# 19_CAN.net
KiCad netlist of a schematic drawn in Altium Designer
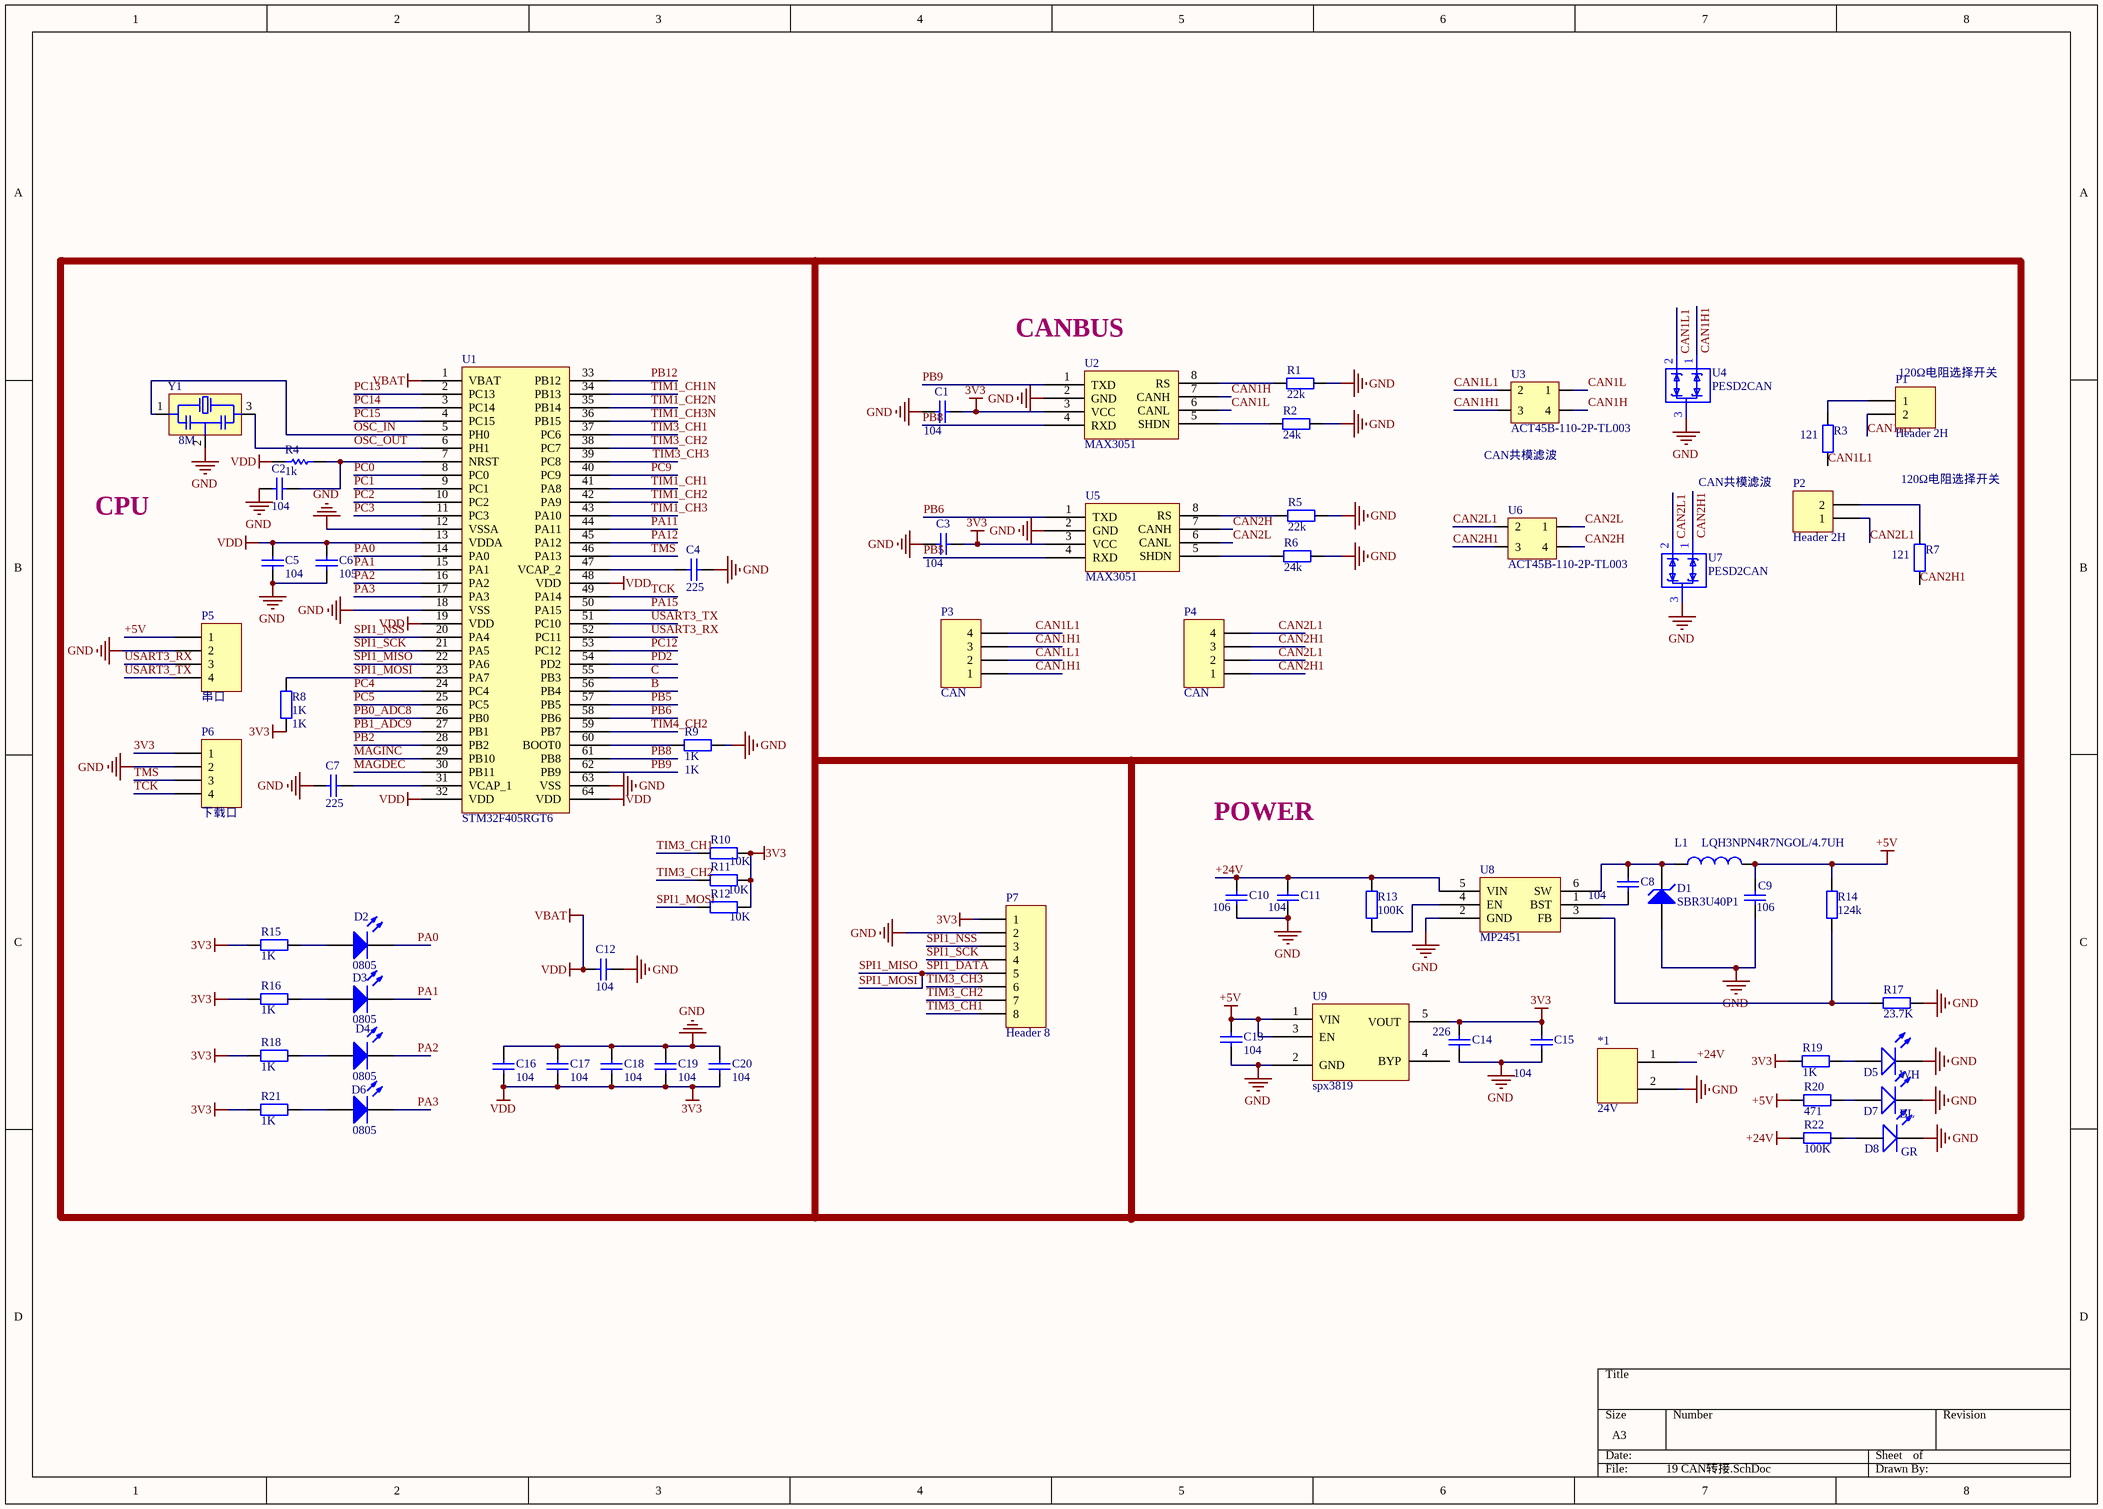
[diagram p0: 19 CAN转接.SchDoc]

(export (version "E")
  (design (tool "Eeschema 10.0.6"))
  (components
    (comp (ref "*1") (value "24V") (footprint "J-XH-2A") (libsource (lib "ACTION原理图库") (part "插件")))
    (comp (ref "C1")
      (value "104")
      (footprint "0402_C")
      (description "贴片电容")
      (libsource (lib "Cap0603") (part "0603 100nF (104) 10% 50V"))
    )
    (comp (ref "C2")
      (value "104")
      (footprint "0603_C")
      (description "Capacitor")
      (libsource (lib "Miscellaneous Devices") (part "Cap"))
    )
    (comp (ref "C3")
      (value "104")
      (footprint "0402_C")
      (description "贴片电容")
      (libsource (lib "Cap0603") (part "0603 100nF (104) 10% 50V"))
    )
    (comp (ref "C4")
      (value "225")
      (footprint "0603_C")
      (description "Capacitor")
      (libsource (lib "Miscellaneous Devices") (part "Cap"))
    )
    (comp (ref "C5")
      (value "104")
      (footprint "0603_C")
      (description "Capacitor")
      (libsource (lib "Miscellaneous Devices") (part "Cap"))
    )
    (comp (ref "C6")
      (value "105")
      (footprint "0603_C")
      (description "Capacitor")
      (libsource (lib "Miscellaneous Devices") (part "Cap"))
    )
    (comp (ref "C7")
      (value "225")
      (footprint "0603_C")
      (description "Capacitor")
      (libsource (lib "Miscellaneous Devices") (part "Cap"))
    )
    (comp (ref "C8")
      (value "104")
      (footprint "0603_C")
      (description "贴片电容")
      (libsource (lib "Cap0603") (part "0603 100nF (104) 10% 50V"))
    )
    (comp (ref "C9")
      (value "106")
      (footprint "0805_C")
      (description "贴片电容")
      (libsource (lib "Cap0805") (part "0805 10uF (106) 10% 25V"))
    )
    (comp (ref "C10")
      (value "106")
      (footprint "0805_C")
      (description "贴片电容")
      (libsource (lib "Cap0805") (part "0805 10uF (106) 10% 25V"))
    )
    (comp (ref "C11")
      (value "104")
      (footprint "0805_C")
      (description "贴片电容")
      (libsource (lib "Cap0805") (part "0805 100nF(104) 10% 50V"))
    )
    (comp (ref "C12")
      (value "104")
      (footprint "0603_C")
      (description "Capacitor")
      (libsource (lib "Miscellaneous Devices") (part "Cap"))
    )
    (comp (ref "C13")
      (value "104")
      (footprint "0603_C")
      (description "贴片电容")
      (libsource (lib "Cap0603") (part "0603 100nF (104) 10% 50V"))
    )
    (comp (ref "C14")
      (value "226")
      (footprint "0603_C")
      (description "贴片电容")
      (libsource (lib "Cap0603") (part "0603 22uF (226) 20% 6.3V"))
    )
    (comp (ref "C15")
      (value "104")
      (footprint "0603_C")
      (description "贴片电容")
      (libsource (lib "Cap0603") (part "0603 100nF (104) 10% 50V"))
    )
    (comp (ref "C16")
      (value "104")
      (footprint "0603_C")
      (description "Capacitor")
      (libsource (lib "Miscellaneous Devices") (part "Cap"))
    )
    (comp (ref "C17")
      (value "104")
      (footprint "0603_C")
      (description "Capacitor")
      (libsource (lib "Miscellaneous Devices") (part "Cap"))
    )
    (comp (ref "C18")
      (value "104")
      (footprint "0603_C")
      (description "Capacitor")
      (libsource (lib "Miscellaneous Devices") (part "Cap"))
    )
    (comp (ref "C19")
      (value "104")
      (footprint "0603_C")
      (description "Capacitor")
      (libsource (lib "Miscellaneous Devices") (part "Cap"))
    )
    (comp (ref "C20")
      (value "104")
      (footprint "0603_C")
      (description "Capacitor")
      (libsource (lib "Miscellaneous Devices") (part "Cap"))
    )
    (comp (ref "D1")
      (value "SBR3U40P1")
      (footprint "D-POWERDI123")
      (description "Zener Diode")
      (libsource (lib "Miscellaneous Devices") (part "D Zener"))
    )
    (comp (ref "D2")
      (value "0805")
      (footprint "0603_LED_S1")
      (description "发光二极管")
      (libsource (lib "LED") (part "0805 蓝灯"))
    )
    (comp (ref "D3")
      (value "0805")
      (footprint "0603_LED_S1")
      (description "发光二极管")
      (libsource (lib "LED") (part "0805 蓝灯"))
    )
    (comp (ref "D4")
      (value "0805")
      (footprint "0603_LED_S1")
      (description "发光二极管")
      (libsource (lib "LED") (part "0805 蓝灯"))
    )
    (comp (ref "D5")
      (value "WH")
      (footprint "0603_LED_S1")
      (description "发光二极管")
      (libsource (lib "LED") (part "0805 白灯"))
    )
    (comp (ref "D6")
      (value "0805")
      (footprint "0603_LED_S1")
      (description "发光二极管")
      (libsource (lib "LED") (part "0805 蓝灯"))
    )
    (comp (ref "D7")
      (value "BL")
      (footprint "0603_LED_S1")
      (description "发光二极管")
      (libsource (lib "LED") (part "0805 白灯"))
    )
    (comp (ref "D8")
      (value "GR")
      (footprint "0603_LED_S1")
      (description "发光二极管")
      (libsource (lib "LED") (part "0805 白灯"))
    )
    (comp (ref "L1")
      (value "LQH3NPN4R7NGOL/4.7UH")
      (footprint "1206_L")
      (description "4.7uh")
      (libsource (lib "Miscellaneous Devices") (part "Inductor"))
    )
    (comp (ref "P1")
      (value "Header 2H")
      (footprint "拨码开关贴片1位 小")
      (description "Header, 2-Pin, Right Angle")
      (fields (field (name "PUBLISHER") "Altium Limited"))
      (libsource (lib "Miscellaneous Connectors") (part "Header 2H"))
    )
    (comp (ref "P2")
      (value "Header 2H")
      (footprint "拨码开关贴片1位 小")
      (description "Header, 2-Pin, Right Angle")
      (fields (field (name "PUBLISHER") "Altium Limited"))
      (libsource (lib "") (part "Header 2H_1"))
    )
    (comp (ref "P3")
      (value "CAN")
      (footprint "J-GH-4P")
      (description "Header, 4-Pin")
      (libsource (lib "ACTION原理图库") (part "J-4PIN"))
    )
    (comp (ref "P4")
      (value "CAN")
      (footprint "J-GH-4P")
      (description "Header, 4-Pin")
      (libsource (lib "ACTION原理图库") (part "J-4PIN"))
    )
    (comp (ref "P5")
      (value "串口")
      (footprint "J-1.27-4P")
      (description "Header, 4-Pin")
      (libsource (lib "Miscellaneous Connectors") (part "Header 4"))
    )
    (comp (ref "P6")
      (value "下载口")
      (footprint "J-1.27-4P")
      (description "Header, 4-Pin")
      (libsource (lib "Miscellaneous Connectors") (part "Header 4"))
    )
    (comp (ref "P7")
      (value "Header 8")
      (footprint "J-GH-8P")
      (description "Header, 8-Pin")
      (fields (field (name "PUBLISHER") "Altium Limited"))
      (libsource (lib "Miscellaneous Connectors") (part "Header 8"))
    )
    (comp (ref "R1")
      (value "22k")
      (footprint "0603_R")
      (description "贴片电阻")
      (libsource (lib "") (part "0603 120Ω (1200) 1%_1"))
    )
    (comp (ref "R2")
      (value "24k")
      (footprint "0603_R")
      (description "贴片电阻")
      (libsource (lib "") (part "0603 120Ω (1200) 1%_2"))
    )
    (comp (ref "R3")
      (value "121")
      (footprint "0603_R")
      (description "贴片电阻")
      (libsource (lib "RES0603") (part "0603 120Ω (1200) 1%"))
    )
    (comp (ref "R4")
      (value "1k")
      (footprint "0603_R")
      (description "Semiconductor Resistor")
      (libsource (lib "大赛无线手柄") (part "Res Semi"))
    )
    (comp (ref "R5")
      (value "22k")
      (footprint "0603_R")
      (description "贴片电阻")
      (libsource (lib "") (part "0603 120Ω (1200) 1%_1"))
    )
    (comp (ref "R6")
      (value "24k")
      (footprint "0603_R")
      (description "贴片电阻")
      (libsource (lib "") (part "0603 120Ω (1200) 1%_2"))
    )
    (comp (ref "R7")
      (value "121")
      (footprint "0603_R")
      (description "贴片电阻")
      (libsource (lib "RES0603") (part "0603 120Ω (1200) 1%"))
    )
    (comp (ref "R8")
      (value "1K")
      (footprint "0603_R")
      (description "Resistor")
      (fields (field (name "ALTIUM_VALUE") "1K"))
      (libsource (lib "Miscellaneous Devices") (part "Res2"))
    )
    (comp (ref "R9")
      (value "1K")
      (footprint "0603_R")
      (description "Resistor")
      (fields (field (name "ALTIUM_VALUE") "1K"))
      (libsource (lib "") (part "Res2_2"))
    )
    (comp (ref "R10")
      (value "10K")
      (footprint "0603_R")
      (description "贴片电阻")
      (libsource (lib "RES0603") (part "0603 1KΩ (1001) 1%"))
    )
    (comp (ref "R11")
      (value "10K")
      (footprint "0603_R")
      (description "贴片电阻")
      (libsource (lib "RES0603") (part "0603 1KΩ (1001) 1%"))
    )
    (comp (ref "R12")
      (value "10K")
      (footprint "0603_R")
      (description "贴片电阻")
      (libsource (lib "RES0603") (part "0603 1KΩ (1001) 1%"))
    )
    (comp (ref "R13")
      (value "100K")
      (footprint "0603_R")
      (description "贴片电阻")
      (libsource (lib "RES0603") (part "0603 100KΩ (1003) 1%"))
    )
    (comp (ref "R14") (value "124k") (footprint "0603_R") (libsource (lib "") (part "Res2_3")))
    (comp (ref "R15")
      (value "1K")
      (footprint "0603_R")
      (description "Resistor")
      (libsource (lib "Free Documents") (part "Res2"))
    )
    (comp (ref "R16")
      (value "1K")
      (footprint "0603_R")
      (description "Resistor")
      (libsource (lib "Free Documents") (part "Res2"))
    )
    (comp (ref "R17")
      (value "23.7K")
      (footprint "0603_R")
      (description "Resistor")
      (libsource (lib "") (part "Res2_1"))
    )
    (comp (ref "R18")
      (value "1K")
      (footprint "0603_R")
      (description "Resistor")
      (libsource (lib "Free Documents") (part "Res2"))
    )
    (comp (ref "R19")
      (value "1K")
      (footprint "0603_R")
      (description "贴片电阻")
      (libsource (lib "RES0603") (part "0603 1KΩ (1001) 1%"))
    )
    (comp (ref "R20")
      (value "471")
      (footprint "0603_R")
      (description "贴片电阻")
      (libsource (lib "RES0603") (part "0603 2KΩ (2001) 1%"))
    )
    (comp (ref "R21")
      (value "1K")
      (footprint "0603_R")
      (description "Resistor")
      (libsource (lib "Free Documents") (part "Res2"))
    )
    (comp (ref "R22")
      (value "100K")
      (footprint "0603_R")
      (description "贴片电阻")
      (libsource (lib "RES0603") (part "0603 10KΩ (1002) 1%"))
    )
    (comp (ref "U1")
      (value "STM32F405RGT6")
      (footprint "LQFP-64")
      (libsource (lib "陀螺仪 元件") (part "STM32F405RGT7"))
    )
    (comp (ref "U2")
      (value "MAX3051")
      (footprint "SOT-23-8")
      (libsource (lib "ACTION原理图库17.7.20修改版") (part "MAX3051EKA"))
    )
    (comp (ref "U3")
      (value "ACT45B-110-2P-TL003")
      (footprint "ACT45B")
      (description "B82793C0/S0")
      (libsource (lib "ACTION原理图库") (part "扼流线圈"))
    )
    (comp (ref "U4") (value "PESD2CAN") (footprint "SOT-233") (libsource (lib "英飞凌电流检测") (part "PESD2CAN")))
    (comp (ref "U5")
      (value "MAX3051")
      (footprint "SOT-23-8")
      (libsource (lib "ACTION原理图库17.7.20修改版") (part "MAX3051EKA"))
    )
    (comp (ref "U6")
      (value "ACT45B-110-2P-TL003")
      (footprint "ACT45B")
      (description "B82793C0/S0")
      (libsource (lib "ACTION原理图库") (part "扼流线圈"))
    )
    (comp (ref "U7") (value "PESD2CAN") (footprint "SOT-233") (libsource (lib "英飞凌电流检测") (part "PESD2CAN")))
    (comp (ref "U8") (value "MP2451") (footprint "SOT-236") (libsource (lib "stm32f103vet6") (part "MP2451")))
    (comp (ref "U9")
      (value "spx3819")
      (footprint "SOT-235")
      (description "spx5205")
      (libsource (lib "无刷01") (part "spx5205"))
    )
    (comp (ref "Y1") (value "8M") (footprint "X-CSTCE8M") (libsource (lib "LPC11Cxx") (part "TXAL-3")))
  )
  (nets
    (net (code "1") (name "+5V") (class "Default")
      (node (ref "C13") (pin "2") (pinfunction "2_2") (pintype "passive"))
      (node (ref "C9") (pin "2") (pinfunction "2_2") (pintype "passive"))
      (node (ref "L1") (pin "2") (pinfunction "2_2") (pintype "passive"))
      (node (ref "P5") (pin "1") (pinfunction "1_1") (pintype "passive"))
      (node (ref "R14") (pin "1") (pinfunction "1_1") (pintype "passive"))
      (node (ref "R20") (pin "1") (pinfunction "1_1") (pintype "passive"))
      (node (ref "U9") (pin "1") (pinfunction "VIN_1") (pintype "passive"))
      (node (ref "U9") (pin "3") (pinfunction "EN_3") (pintype "passive"))
    )
    (net (code "2") (name "+24V") (class "Default")
      (node (ref "*1") (pin "1") (pintype "passive"))
      (node (ref "C10") (pin "2") (pinfunction "2_2") (pintype "passive"))
      (node (ref "C11") (pin "2") (pinfunction "2_2") (pintype "passive"))
      (node (ref "R13") (pin "2") (pinfunction "2_2") (pintype "passive"))
      (node (ref "R22") (pin "1") (pinfunction "1_1") (pintype "passive"))
      (node (ref "U8") (pin "5") (pinfunction "VIN_5") (pintype "passive"))
    )
    (net (code "3") (name "/B") (class "Default")
      (node (ref "U1") (pin "56") (pinfunction "PB4_56") (pintype "passive"))
    )
    (net (code "4") (name "/C") (class "Default")
      (node (ref "U1") (pin "55") (pinfunction "PB3_55") (pintype "passive"))
    )
    (net (code "5") (name "/CAN1H") (class "Default")
      (node (ref "U2") (pin "7") (pinfunction "CANH_7") (pintype "passive"))
      (node (ref "U3") (pin "4") (pinfunction "4_4") (pintype "passive"))
    )
    (net (code "6") (name "/CAN1H1") (class "Default")
      (node (ref "P1") (pin "2") (pinfunction "2_2") (pintype "passive"))
      (node (ref "P3") (pin "1") (pinfunction "1_1") (pintype "passive"))
      (node (ref "P3") (pin "3") (pinfunction "3_3") (pintype "passive"))
      (node (ref "U3") (pin "3") (pinfunction "3_3") (pintype "passive"))
      (node (ref "U4") (pin "1") (pinfunction "1_1") (pintype "passive"))
    )
    (net (code "7") (name "/CAN1L") (class "Default")
      (node (ref "U2") (pin "6") (pinfunction "CANL_6") (pintype "passive"))
      (node (ref "U3") (pin "1") (pinfunction "1_1") (pintype "passive"))
    )
    (net (code "8") (name "/CAN1L1") (class "Default")
      (node (ref "P3") (pin "2") (pinfunction "2_2") (pintype "passive"))
      (node (ref "P3") (pin "4") (pinfunction "4_4") (pintype "passive"))
      (node (ref "R3") (pin "1") (pinfunction "1_1") (pintype "passive"))
      (node (ref "U3") (pin "2") (pinfunction "2_2") (pintype "passive"))
      (node (ref "U4") (pin "2") (pinfunction "2_2") (pintype "passive"))
    )
    (net (code "9") (name "/CAN2H") (class "Default")
      (node (ref "U5") (pin "7") (pinfunction "CANH_7") (pintype "passive"))
      (node (ref "U6") (pin "4") (pinfunction "4_4") (pintype "passive"))
    )
    (net (code "10") (name "/CAN2H1") (class "Default")
      (node (ref "P4") (pin "1") (pinfunction "1_1") (pintype "passive"))
      (node (ref "P4") (pin "3") (pinfunction "3_3") (pintype "passive"))
      (node (ref "R7") (pin "1") (pinfunction "1_1") (pintype "passive"))
      (node (ref "U6") (pin "3") (pinfunction "3_3") (pintype "passive"))
      (node (ref "U7") (pin "1") (pinfunction "1_1") (pintype "passive"))
    )
    (net (code "11") (name "/CAN2L") (class "Default")
      (node (ref "U5") (pin "6") (pinfunction "CANL_6") (pintype "passive"))
      (node (ref "U6") (pin "1") (pinfunction "1_1") (pintype "passive"))
    )
    (net (code "12") (name "/CAN2L1") (class "Default")
      (node (ref "P2") (pin "1") (pinfunction "1_1") (pintype "passive"))
      (node (ref "P4") (pin "2") (pinfunction "2_2") (pintype "passive"))
      (node (ref "P4") (pin "4") (pinfunction "4_4") (pintype "passive"))
      (node (ref "U6") (pin "2") (pinfunction "2_2") (pintype "passive"))
      (node (ref "U7") (pin "2") (pinfunction "2_2") (pintype "passive"))
    )
    (net (code "13") (name "/MAGDEC") (class "Default")
      (node (ref "U1") (pin "30") (pinfunction "PB11_30") (pintype "passive"))
    )
    (net (code "14") (name "/MAGINC") (class "Default")
      (node (ref "U1") (pin "29") (pinfunction "PB10_29") (pintype "passive"))
    )
    (net (code "15") (name "/OSC_IN") (class "Default")
      (node (ref "U1") (pin "5") (pinfunction "PH0_5") (pintype "passive"))
      (node (ref "Y1") (pin "1") (pinfunction "OSCIN_1") (pintype "passive"))
    )
    (net (code "16") (name "/OSC_OUT") (class "Default")
      (node (ref "U1") (pin "6") (pinfunction "PH1_6") (pintype "passive"))
      (node (ref "Y1") (pin "3") (pinfunction "OSCOUT_3") (pintype "passive"))
    )
    (net (code "17") (name "/PA0") (class "Default")
      (node (ref "D2") (pin "K") (pinfunction "K_K") (pintype "passive"))
      (node (ref "U1") (pin "14") (pinfunction "PA0_14") (pintype "passive"))
    )
    (net (code "18") (name "/PA1") (class "Default")
      (node (ref "D3") (pin "K") (pinfunction "K_K") (pintype "passive"))
      (node (ref "U1") (pin "15") (pinfunction "PA1_15") (pintype "passive"))
    )
    (net (code "19") (name "/PA2") (class "Default")
      (node (ref "D4") (pin "K") (pinfunction "K_K") (pintype "passive"))
      (node (ref "U1") (pin "16") (pinfunction "PA2_16") (pintype "passive"))
    )
    (net (code "20") (name "/PA3") (class "Default")
      (node (ref "D6") (pin "K") (pinfunction "K_K") (pintype "passive"))
      (node (ref "U1") (pin "17") (pinfunction "PA3_17") (pintype "passive"))
    )
    (net (code "21") (name "/PA11") (class "Default")
      (node (ref "U1") (pin "44") (pinfunction "PA11_44") (pintype "passive"))
    )
    (net (code "22") (name "/PA12") (class "Default")
      (node (ref "U1") (pin "45") (pinfunction "PA12_45") (pintype "passive"))
    )
    (net (code "23") (name "/PA15") (class "Default")
      (node (ref "U1") (pin "50") (pinfunction "PA15_50") (pintype "passive"))
    )
    (net (code "24") (name "/PB0_ADC8") (class "Default")
      (node (ref "U1") (pin "26") (pinfunction "PB0_26") (pintype "passive"))
    )
    (net (code "25") (name "/PB1_ADC9") (class "Default")
      (node (ref "U1") (pin "27") (pinfunction "PB1_27") (pintype "passive"))
    )
    (net (code "26") (name "/PB2") (class "Default")
      (node (ref "U1") (pin "28") (pinfunction "PB2_28") (pintype "passive"))
    )
    (net (code "27") (name "/PB5") (class "Default")
      (node (ref "U1") (pin "57") (pinfunction "PB5_57") (pintype "passive"))
      (node (ref "U5") (pin "4") (pinfunction "RXD_4") (pintype "passive"))
    )
    (net (code "28") (name "/PB6") (class "Default")
      (node (ref "U1") (pin "58") (pinfunction "PB6_58") (pintype "passive"))
      (node (ref "U5") (pin "1") (pinfunction "TXD_1") (pintype "passive"))
    )
    (net (code "29") (name "/PB8") (class "Default")
      (node (ref "U1") (pin "61") (pinfunction "PB8_61") (pintype "passive"))
      (node (ref "U2") (pin "4") (pinfunction "RXD_4") (pintype "passive"))
    )
    (net (code "30") (name "/PB9") (class "Default")
      (node (ref "U1") (pin "62") (pinfunction "PB9_62") (pintype "passive"))
      (node (ref "U2") (pin "1") (pinfunction "TXD_1") (pintype "passive"))
    )
    (net (code "31") (name "/PB12") (class "Default")
      (node (ref "U1") (pin "33") (pinfunction "PB12_33") (pintype "passive"))
    )
    (net (code "32") (name "/PC0") (class "Default")
      (node (ref "U1") (pin "8") (pinfunction "PC0_8") (pintype "passive"))
    )
    (net (code "33") (name "/PC1") (class "Default")
      (node (ref "U1") (pin "9") (pinfunction "PC1_9") (pintype "passive"))
    )
    (net (code "34") (name "/PC2") (class "Default")
      (node (ref "U1") (pin "10") (pinfunction "PC2_10") (pintype "passive"))
    )
    (net (code "35") (name "/PC3") (class "Default")
      (node (ref "U1") (pin "11") (pinfunction "PC3_11") (pintype "passive"))
    )
    (net (code "36") (name "/PC4") (class "Default")
      (node (ref "U1") (pin "24") (pinfunction "PC4_24") (pintype "passive"))
    )
    (net (code "37") (name "/PC5") (class "Default")
      (node (ref "U1") (pin "25") (pinfunction "PC5_25") (pintype "passive"))
    )
    (net (code "38") (name "/PC9") (class "Default")
      (node (ref "U1") (pin "40") (pinfunction "PC9_40") (pintype "passive"))
    )
    (net (code "39") (name "/PC12") (class "Default")
      (node (ref "U1") (pin "53") (pinfunction "PC12_53") (pintype "passive"))
    )
    (net (code "40") (name "/PC13") (class "Default")
      (node (ref "U1") (pin "2") (pinfunction "PC13_2") (pintype "passive"))
    )
    (net (code "41") (name "/PC14") (class "Default")
      (node (ref "U1") (pin "3") (pinfunction "PC14_3") (pintype "passive"))
    )
    (net (code "42") (name "/PC15") (class "Default")
      (node (ref "U1") (pin "4") (pinfunction "PC15_4") (pintype "passive"))
    )
    (net (code "43") (name "/PD2") (class "Default")
      (node (ref "U1") (pin "54") (pinfunction "PD2_54") (pintype "passive"))
    )
    (net (code "44") (name "/SPI1_DATA") (class "Default")
      (node (ref "P7") (pin "5") (pinfunction "5_5") (pintype "passive"))
      (node (ref "R12") (pin "1") (pinfunction "1_1") (pintype "passive"))
      (node (ref "R8") (pin "2") (pinfunction "2_2") (pintype "passive"))
      (node (ref "U1") (pin "22") (pinfunction "PA6_22") (pintype "passive"))
      (node (ref "U1") (pin "23") (pinfunction "PA7_23") (pintype "passive"))
    )
    (net (code "45") (name "/SPI1_NSS") (class "Default")
      (node (ref "P7") (pin "3") (pinfunction "3_3") (pintype "passive"))
      (node (ref "U1") (pin "20") (pinfunction "PA4_20") (pintype "passive"))
    )
    (net (code "46") (name "/SPI1_SCK") (class "Default")
      (node (ref "P7") (pin "4") (pinfunction "4_4") (pintype "passive"))
      (node (ref "U1") (pin "21") (pinfunction "PA5_21") (pintype "passive"))
    )
    (net (code "47") (name "/TCK") (class "Default")
      (node (ref "P6") (pin "4") (pinfunction "4_4") (pintype "passive"))
      (node (ref "U1") (pin "49") (pinfunction "PA14_49") (pintype "passive"))
    )
    (net (code "48") (name "/TIM1_CH1") (class "Default")
      (node (ref "U1") (pin "41") (pinfunction "PA8_41") (pintype "passive"))
    )
    (net (code "49") (name "/TIM1_CH1N") (class "Default")
      (node (ref "U1") (pin "34") (pinfunction "PB13_34") (pintype "passive"))
    )
    (net (code "50") (name "/TIM1_CH2") (class "Default")
      (node (ref "U1") (pin "42") (pinfunction "PA9_42") (pintype "passive"))
    )
    (net (code "51") (name "/TIM1_CH2N") (class "Default")
      (node (ref "U1") (pin "35") (pinfunction "PB14_35") (pintype "passive"))
    )
    (net (code "52") (name "/TIM1_CH3") (class "Default")
      (node (ref "U1") (pin "43") (pinfunction "PA10_43") (pintype "passive"))
    )
    (net (code "53") (name "/TIM1_CH3N") (class "Default")
      (node (ref "U1") (pin "36") (pinfunction "PB15_36") (pintype "passive"))
    )
    (net (code "54") (name "/TIM3_CH1") (class "Default")
      (node (ref "P7") (pin "8") (pinfunction "8_8") (pintype "passive"))
      (node (ref "R10") (pin "1") (pinfunction "1_1") (pintype "passive"))
      (node (ref "U1") (pin "37") (pinfunction "PC6_37") (pintype "passive"))
    )
    (net (code "55") (name "/TIM3_CH2") (class "Default")
      (node (ref "P7") (pin "7") (pinfunction "7_7") (pintype "passive"))
      (node (ref "R11") (pin "1") (pinfunction "1_1") (pintype "passive"))
      (node (ref "U1") (pin "38") (pinfunction "PC7_38") (pintype "passive"))
    )
    (net (code "56") (name "/TIM3_CH3") (class "Default")
      (node (ref "P7") (pin "6") (pinfunction "6_6") (pintype "passive"))
      (node (ref "U1") (pin "39") (pinfunction "PC8_39") (pintype "passive"))
    )
    (net (code "57") (name "/TIM4_CH2") (class "Default")
      (node (ref "U1") (pin "59") (pinfunction "PB7_59") (pintype "passive"))
    )
    (net (code "58") (name "/TMS") (class "Default")
      (node (ref "P6") (pin "3") (pinfunction "3_3") (pintype "passive"))
      (node (ref "U1") (pin "46") (pinfunction "PA13_46") (pintype "passive"))
    )
    (net (code "59") (name "/USART3_RX") (class "Default")
      (node (ref "P5") (pin "3") (pinfunction "3_3") (pintype "passive"))
      (node (ref "U1") (pin "52") (pinfunction "PC11_52") (pintype "passive"))
    )
    (net (code "60") (name "/USART3_TX") (class "Default")
      (node (ref "P5") (pin "4") (pinfunction "4_4") (pintype "passive"))
      (node (ref "U1") (pin "51") (pinfunction "PC10_51") (pintype "passive"))
    )
    (net (code "61") (name "3V3") (class "Default")
      (node (ref "C1") (pin "2") (pinfunction "2_2") (pintype "passive"))
      (node (ref "C12") (pin "1") (pinfunction "1_1") (pintype "passive"))
      (node (ref "C14") (pin "2") (pinfunction "2_2") (pintype "passive"))
      (node (ref "C15") (pin "2") (pinfunction "2_2") (pintype "passive"))
      (node (ref "C16") (pin "1") (pinfunction "1_1") (pintype "passive"))
      (node (ref "C17") (pin "1") (pinfunction "1_1") (pintype "passive"))
      (node (ref "C18") (pin "1") (pinfunction "1_1") (pintype "passive"))
      (node (ref "C19") (pin "1") (pinfunction "1_1") (pintype "passive"))
      (node (ref "C20") (pin "1") (pinfunction "1_1") (pintype "passive"))
      (node (ref "C3") (pin "2") (pinfunction "2_2") (pintype "passive"))
      (node (ref "C5") (pin "1") (pinfunction "1_1") (pintype "passive"))
      (node (ref "C6") (pin "1") (pinfunction "1_1") (pintype "passive"))
      (node (ref "P6") (pin "1") (pinfunction "1_1") (pintype "passive"))
      (node (ref "P7") (pin "1") (pinfunction "1_1") (pintype "passive"))
      (node (ref "R10") (pin "2") (pinfunction "2_2") (pintype "passive"))
      (node (ref "R11") (pin "2") (pinfunction "2_2") (pintype "passive"))
      (node (ref "R12") (pin "2") (pinfunction "2_2") (pintype "passive"))
      (node (ref "R15") (pin "1") (pinfunction "1_1") (pintype "passive"))
      (node (ref "R16") (pin "1") (pinfunction "1_1") (pintype "passive"))
      (node (ref "R18") (pin "1") (pinfunction "1_1") (pintype "passive"))
      (node (ref "R19") (pin "1") (pinfunction "1_1") (pintype "passive"))
      (node (ref "R21") (pin "1") (pinfunction "1_1") (pintype "passive"))
      (node (ref "R4") (pin "2") (pinfunction "2_2") (pintype "passive"))
      (node (ref "R8") (pin "1") (pinfunction "1_1") (pintype "passive"))
      (node (ref "U1") (pin "1") (pinfunction "VBAT_1") (pintype "passive"))
      (node (ref "U1") (pin "13") (pinfunction "VDDA_13") (pintype "passive"))
      (node (ref "U1") (pin "19") (pinfunction "VDD_19") (pintype "passive"))
      (node (ref "U1") (pin "32") (pinfunction "VDD_32") (pintype "passive"))
      (node (ref "U1") (pin "48") (pinfunction "VDD_48") (pintype "passive"))
      (node (ref "U1") (pin "64") (pinfunction "VDD_64") (pintype "passive"))
      (node (ref "U2") (pin "3") (pinfunction "VCC_3") (pintype "passive"))
      (node (ref "U5") (pin "3") (pinfunction "VCC_3") (pintype "passive"))
      (node (ref "U9") (pin "5") (pinfunction "VOUT_5") (pintype "passive"))
    )
    (net (code "62") (name "GND") (class "Default")
      (node (ref "*1") (pin "2") (pintype "passive"))
      (node (ref "C1") (pin "1") (pinfunction "1_1") (pintype "passive"))
      (node (ref "C10") (pin "1") (pinfunction "1_1") (pintype "passive"))
      (node (ref "C11") (pin "1") (pinfunction "1_1") (pintype "passive"))
      (node (ref "C12") (pin "2") (pinfunction "2_2") (pintype "passive"))
      (node (ref "C13") (pin "1") (pinfunction "1_1") (pintype "passive"))
      (node (ref "C14") (pin "1") (pinfunction "1_1") (pintype "passive"))
      (node (ref "C15") (pin "1") (pinfunction "1_1") (pintype "passive"))
      (node (ref "C16") (pin "2") (pinfunction "2_2") (pintype "passive"))
      (node (ref "C17") (pin "2") (pinfunction "2_2") (pintype "passive"))
      (node (ref "C18") (pin "2") (pinfunction "2_2") (pintype "passive"))
      (node (ref "C19") (pin "2") (pinfunction "2_2") (pintype "passive"))
      (node (ref "C2") (pin "1") (pinfunction "1_1") (pintype "passive"))
      (node (ref "C20") (pin "2") (pinfunction "2_2") (pintype "passive"))
      (node (ref "C3") (pin "1") (pinfunction "1_1") (pintype "passive"))
      (node (ref "C4") (pin "2") (pinfunction "2_2") (pintype "passive"))
      (node (ref "C5") (pin "2") (pinfunction "2_2") (pintype "passive"))
      (node (ref "C6") (pin "2") (pinfunction "2_2") (pintype "passive"))
      (node (ref "C7") (pin "1") (pinfunction "1_1") (pintype "passive"))
      (node (ref "C9") (pin "1") (pinfunction "1_1") (pintype "passive"))
      (node (ref "D1") (pin "1") (pinfunction "A_1") (pintype "passive"))
      (node (ref "D5") (pin "K") (pinfunction "K_K") (pintype "passive"))
      (node (ref "D7") (pin "K") (pinfunction "K_K") (pintype "passive"))
      (node (ref "D8") (pin "K") (pinfunction "K_K") (pintype "passive"))
      (node (ref "P5") (pin "2") (pinfunction "2_2") (pintype "passive"))
      (node (ref "P6") (pin "2") (pinfunction "2_2") (pintype "passive"))
      (node (ref "P7") (pin "2") (pinfunction "2_2") (pintype "passive"))
      (node (ref "R1") (pin "1") (pinfunction "1_1") (pintype "passive"))
      (node (ref "R17") (pin "1") (pinfunction "1_1") (pintype "passive"))
      (node (ref "R2") (pin "2") (pinfunction "2_2") (pintype "passive"))
      (node (ref "R5") (pin "1") (pinfunction "1_1") (pintype "passive"))
      (node (ref "R6") (pin "2") (pinfunction "2_2") (pintype "passive"))
      (node (ref "R9") (pin "2") (pinfunction "2_2") (pintype "passive"))
      (node (ref "U1") (pin "12") (pinfunction "VSSA_12") (pintype "passive"))
      (node (ref "U1") (pin "18") (pinfunction "VSS_18") (pintype "passive"))
      (node (ref "U1") (pin "63") (pinfunction "VSS_63") (pintype "passive"))
      (node (ref "U2") (pin "2") (pinfunction "GND_2") (pintype "passive"))
      (node (ref "U4") (pin "3") (pinfunction "3_3") (pintype "passive"))
      (node (ref "U5") (pin "2") (pinfunction "GND_2") (pintype "passive"))
      (node (ref "U7") (pin "3") (pinfunction "3_3") (pintype "passive"))
      (node (ref "U8") (pin "2") (pinfunction "GND_2") (pintype "passive"))
      (node (ref "U9") (pin "2") (pinfunction "GND_2") (pintype "passive"))
      (node (ref "Y1") (pin "2") (pinfunction "GND_2") (pintype "passive"))
    )
    (net (code "63") (name "Net-(D1-K)") (class "Default")
      (node (ref "C8") (pin "2") (pinfunction "2_2") (pintype "passive"))
      (node (ref "D1") (pin "2") (pinfunction "K_2") (pintype "passive"))
      (node (ref "L1") (pin "1") (pinfunction "1_1") (pintype "passive"))
      (node (ref "U8") (pin "6") (pinfunction "SW_6") (pintype "passive"))
    )
    (net (code "64") (name "Net-(D2-PadA)") (class "Default")
      (node (ref "D2") (pin "A") (pinfunction "A_A") (pintype "passive"))
      (node (ref "R15") (pin "2") (pinfunction "2_2") (pintype "passive"))
    )
    (net (code "65") (name "Net-(D3-PadA)") (class "Default")
      (node (ref "D3") (pin "A") (pinfunction "A_A") (pintype "passive"))
      (node (ref "R16") (pin "2") (pinfunction "2_2") (pintype "passive"))
    )
    (net (code "66") (name "Net-(D4-PadA)") (class "Default")
      (node (ref "D4") (pin "A") (pinfunction "A_A") (pintype "passive"))
      (node (ref "R18") (pin "2") (pinfunction "2_2") (pintype "passive"))
    )
    (net (code "67") (name "Net-(D5-PadA)") (class "Default")
      (node (ref "D5") (pin "A") (pinfunction "A_A") (pintype "passive"))
      (node (ref "R19") (pin "2") (pinfunction "2_2") (pintype "passive"))
    )
    (net (code "68") (name "Net-(D6-PadA)") (class "Default")
      (node (ref "D6") (pin "A") (pinfunction "A_A") (pintype "passive"))
      (node (ref "R21") (pin "2") (pinfunction "2_2") (pintype "passive"))
    )
    (net (code "69") (name "Net-(D7-PadA)") (class "Default")
      (node (ref "D7") (pin "A") (pinfunction "A_A") (pintype "passive"))
      (node (ref "R20") (pin "2") (pinfunction "2_2") (pintype "passive"))
    )
    (net (code "70") (name "Net-(D8-PadA)") (class "Default")
      (node (ref "D8") (pin "A") (pinfunction "A_A") (pintype "passive"))
      (node (ref "R22") (pin "2") (pinfunction "2_2") (pintype "passive"))
    )
    (net (code "71") (name "Net-(P1-Pad1)") (class "Default")
      (node (ref "P1") (pin "1") (pinfunction "1_1") (pintype "passive"))
      (node (ref "R3") (pin "2") (pinfunction "2_2") (pintype "passive"))
    )
    (net (code "72") (name "Net-(P2-Pad2)") (class "Default")
      (node (ref "P2") (pin "2") (pinfunction "2_2") (pintype "passive"))
      (node (ref "R7") (pin "2") (pinfunction "2_2") (pintype "passive"))
    )
    (net (code "73") (name "Net-(U1-BOOT0)") (class "Default")
      (node (ref "R9") (pin "1") (pinfunction "1_1") (pintype "passive"))
      (node (ref "U1") (pin "60") (pinfunction "BOOT0_60") (pintype "passive"))
    )
    (net (code "74") (name "Net-(U1-NRST)") (class "Default")
      (node (ref "C2") (pin "2") (pinfunction "2_2") (pintype "passive"))
      (node (ref "R4") (pin "1") (pinfunction "1_1") (pintype "passive"))
      (node (ref "U1") (pin "7") (pinfunction "NRST_7") (pintype "passive"))
    )
    (net (code "75") (name "Net-(U1-VCAP_1)") (class "Default")
      (node (ref "C7") (pin "2") (pinfunction "2_2") (pintype "passive"))
      (node (ref "U1") (pin "31") (pinfunction "VCAP_1_31") (pintype "passive"))
    )
    (net (code "76") (name "Net-(U1-VCAP_2)") (class "Default")
      (node (ref "C4") (pin "1") (pinfunction "1_1") (pintype "passive"))
      (node (ref "U1") (pin "47") (pinfunction "VCAP_2_47") (pintype "passive"))
    )
    (net (code "77") (name "Net-(U2-RS)") (class "Default")
      (node (ref "R1") (pin "2") (pinfunction "2_2") (pintype "passive"))
      (node (ref "U2") (pin "8") (pinfunction "RS_8") (pintype "passive"))
    )
    (net (code "78") (name "Net-(U2-SHDN)") (class "Default")
      (node (ref "R2") (pin "1") (pinfunction "1_1") (pintype "passive"))
      (node (ref "U2") (pin "5") (pinfunction "SHDN_5") (pintype "passive"))
    )
    (net (code "79") (name "Net-(U5-RS)") (class "Default")
      (node (ref "R5") (pin "2") (pinfunction "2_2") (pintype "passive"))
      (node (ref "U5") (pin "8") (pinfunction "RS_8") (pintype "passive"))
    )
    (net (code "80") (name "Net-(U5-SHDN)") (class "Default")
      (node (ref "R6") (pin "1") (pinfunction "1_1") (pintype "passive"))
      (node (ref "U5") (pin "5") (pinfunction "SHDN_5") (pintype "passive"))
    )
    (net (code "81") (name "Net-(U8-BST)") (class "Default")
      (node (ref "C8") (pin "1") (pinfunction "1_1") (pintype "passive"))
      (node (ref "U8") (pin "1") (pinfunction "BST_1") (pintype "passive"))
    )
    (net (code "82") (name "Net-(U8-EN)") (class "Default")
      (node (ref "R13") (pin "1") (pinfunction "1_1") (pintype "passive"))
      (node (ref "U8") (pin "4") (pinfunction "EN_4") (pintype "passive"))
    )
    (net (code "83") (name "Net-(U8-FB)") (class "Default")
      (node (ref "R14") (pin "2") (pinfunction "2_2") (pintype "passive"))
      (node (ref "R17") (pin "2") (pinfunction "2_2") (pintype "passive"))
      (node (ref "U8") (pin "3") (pinfunction "FB_3") (pintype "passive"))
    )
    (net (code "84") (name "unconnected-(U9-BYP-Pad4)") (class "Default")
      (node (ref "U9") (pin "4") (pinfunction "BYP_4") (pintype "passive"))
    )
  )
)
